# design.net
KiCad netlist of a schematic drawn in Altium Designer
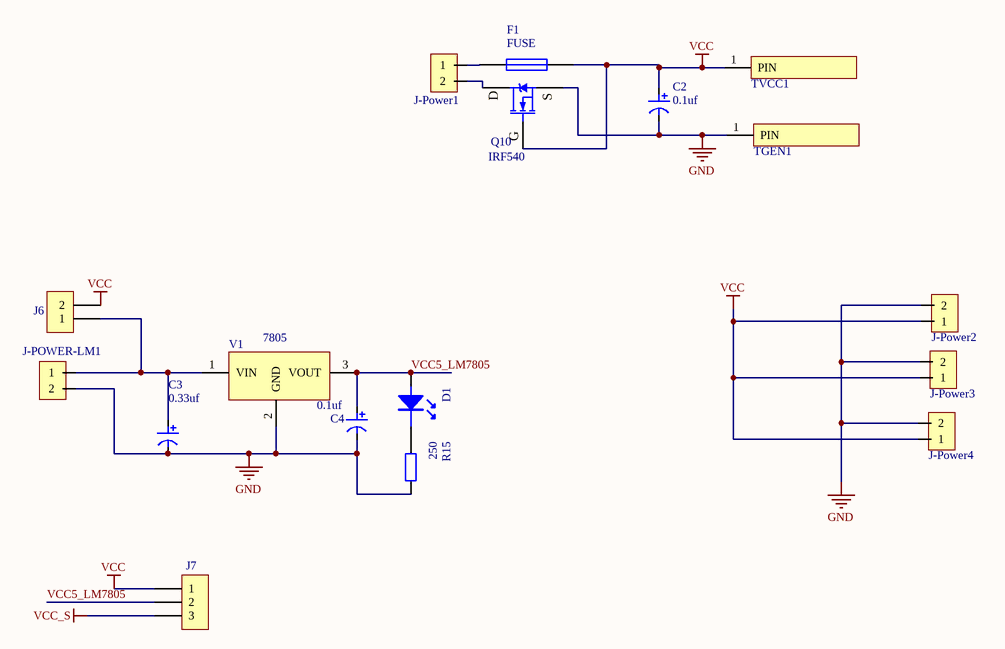
[diagram p0: 电源.SchDoc]

(export (version "E")
  (design (tool "Eeschema 10.0.6"))
  (components
    (comp (ref "C2")
      (value "0.1uf")
      (footprint "CE5-6R5X5-1mm")
      (description "DIP,电容量681pf,额定电压2000V,偏差±10%,6.5X5mm")
      (fields
        (field (name "PART NUMBER") "102CB-00002OD.01")
        (field (name "ALLOW ALTENATIVE PART") "Y")
        (field (name "REMARK") "Verified by BU1（黄雄青） check list V1.0")
        (field (name "MODIFY TIME") "2015年11月05号")
        (field (name "APPROVED") "YES")
      )
      (libsource (lib "IA-04") (part "CAP_Alum-2-N2"))
    )
    (comp (ref "C3")
      (value "0.33uf")
      (footprint "CE5-6R5X5-1mm")
      (description "DIP,电容量681pf,额定电压2000V,偏差±10%,6.5X5mm")
      (fields
        (field (name "PART NUMBER") "102CB-00002OD.01")
        (field (name "ALLOW ALTENATIVE PART") "Y")
        (field (name "REMARK") "Verified by BU1（黄雄青） check list V1.0")
        (field (name "MODIFY TIME") "2015年11月05号")
        (field (name "APPROVED") "YES")
      )
      (libsource (lib "IA-04") (part "CAP_Alum-2-N2"))
    )
    (comp (ref "C4")
      (value "0.1uf")
      (footprint "CE5-6R5X5-1mm")
      (description "DIP,电容量681pf,额定电压2000V,偏差±10%,6.5X5mm")
      (fields
        (field (name "PART NUMBER") "102CB-00002OD.01")
        (field (name "ALLOW ALTENATIVE PART") "Y")
        (field (name "REMARK") "Verified by BU1（黄雄青） check list V1.0")
        (field (name "MODIFY TIME") "2015年11月05号")
        (field (name "APPROVED") "YES")
      )
      (libsource (lib "IA-04") (part "CAP_Alum-2-N2"))
    )
    (comp (ref "D1")
      (value "333-2SYGD/S530-E2")
      (footprint "LED2-D5R9X8R7")
      (description "DIP,封装/间距直径5/2.54mm,额定电压2V,亮度普亮,绿色")
      (fields
        (field (name "PART NUMBER") "102DL-00010CH.01")
        (field (name "ALLOW ALTENATIVE PART") "Y")
        (field (name "REMARK") "Verified by CRD（张宗良） check list V1.0")
        (field (name "MODIFY TIME") "2015年11月11号")
        (field (name "APPROVED") "YES")
      )
      (libsource (lib "IA-04") (part "Diode-LED-2-N2"))
    )
    (comp (ref "F1")
      (value "FUSE")
      (footprint "FUSE-24R1X3RX29R7-TH")
      (description "DIP,24.1x29.7x3.0mm,额定电压30V,额定电流9A,触发电流18A,中速断")
      (fields
        (field (name "PART NUMBER") "102FP-00037BI.01")
        (field (name "ALLOW ALTENATIVE PART") "Y")
        (field (name "REMARK") "Verified by BU1（黄雄青） check list V1.0")
        (field (name "MODIFY TIME") "2015年07月10号")
        (field (name "APPROVED") "YES")
      )
      (libsource (lib "IA-04") (part "Fuse-2-NP"))
    )
    (comp (ref "J-POWER-LM1")
      (value "KF301-5.08-2p")
      (footprint "KF301-5.0-2P")
      (libsource (lib "") (part "KF301_1"))
    )
    (comp (ref "J-Power1")
      (value "KF301-5.08-2p")
      (footprint "KF301-5.0-2P")
      (libsource (lib "") (part "KF301_1"))
    )
    (comp (ref "J-Power2")
      (value "KF301-5.08-2p")
      (footprint "KF301-5.0-2P")
      (libsource (lib "KF接口") (part "KF301"))
    )
    (comp (ref "J-Power3")
      (value "KF301-5.08-2p")
      (footprint "KF301-5.0-2P")
      (libsource (lib "KF接口") (part "KF301"))
    )
    (comp (ref "J-Power4")
      (value "KF301-5.08-2p")
      (footprint "KF301-5.0-2P")
      (libsource (lib "KF接口") (part "KF301"))
    )
    (comp (ref "J6")
      (value "PAS1251-0201A01B1BA")
      (footprint "CON2P-2R54-TH")
      (description "DIP,封装脚距2.54mm,180度,1x2PIN,上针/下针6.0/3.0mm,黑色")
      (fields
        (field (name "PART NUMBER") "102NL-00005DJ.01")
        (field (name "ALLOW ALTENATIVE PART") "Y")
        (field (name "REMARK") "Verified by BU2（叶俊雄） check list V1.0")
        (field (name "MODIFY TIME") "2016年08月22号")
        (field (name "APPROVED") "YES")
      )
      (libsource (lib "IA-04") (part "CON2P-NP"))
    )
    (comp (ref "J7")
      (value "PAS1251-0301A01B1BA")
      (footprint "CON3P-2R54-TH")
      (description "DIP,封装脚距2.54mm,180度,1x3PIN,黑色")
      (fields
        (field (name "PART NUMBER") "102NL-00001DJ.01")
        (field (name "ALLOW ALTENATIVE PART") "Y")
        (field (name "REMARK") "Verified by CRD（赖程奇） check list V1.0")
        (field (name "MODIFY TIME") "2016年1月11号")
        (field (name "APPROVED") "YES")
      )
      (libsource (lib "IA-04") (part "CON3-NP"))
    )
    (comp (ref "Q10")
      (value "IRF540")
      (footprint "TO220A")
      (description "N沟场效应管")
      (fields (field (name "版权归属") "源创客"))
      (libsource (lib "6.1   - 场效应管-可控硅") (part "IRF840"))
    )
    (comp (ref "R15")
      (value "250")
      (footprint "RY0R25W")
      (description "DIP,阻值500R,精度±0.1%,4.75x1.65mm,额定功率1/4W")
      (fields
        (field (name "PART NUMBER") "102RO-00087BS.01")
        (field (name "ALLOW ALTENATIVE PART") "Y")
        (field (name "REMARK") "Verified by BU3（吴明徽）check list V1.0")
        (field (name "MODIFY TIME") "2015年11月30号")
        (field (name "APPROVED") "YES")
      )
      (libsource (lib "IA-04") (part "RES-2-NP"))
    )
    (comp (ref "TGEN1")
      (value "T？")
      (footprint "铺铜条")
      (description "2mm*20的铜条用于焊接")
      (libsource (lib "KF接口") (part "铺铜条"))
    )
    (comp (ref "TVCC1")
      (value "T？")
      (footprint "铺铜条")
      (description "2mm*20的铜条用于焊接")
      (libsource (lib "KF接口") (part "铺铜条"))
    )
    (comp (ref "V1")
      (value "7805")
      (footprint "TO220A")
      (description "线性稳压芯片")
      (fields (field (name "版权归属") "源创客"))
      (libsource (lib "1.3   - 电源类芯片") (part "78xx"))
    )
  )
  (nets
    (net (code "1") (name "/VCC5_LM7805") (class "Default")
      (node (ref "C4") (pin "1") (pinfunction "1_1") (pintype "passive"))
      (node (ref "D1") (pin "1") (pinfunction "1_1") (pintype "passive"))
      (node (ref "J7") (pin "2") (pinfunction "2_2") (pintype "passive"))
      (node (ref "V1") (pin "3") (pinfunction "VOUT_3") (pintype "passive"))
    )
    (net (code "2") (name "GND") (class "Default")
      (node (ref "C2") (pin "2") (pinfunction "2_2") (pintype "passive"))
      (node (ref "C3") (pin "2") (pinfunction "2_2") (pintype "passive"))
      (node (ref "C4") (pin "2") (pinfunction "2_2") (pintype "passive"))
      (node (ref "J-POWER-LM1") (pin "2") (pinfunction "2_2") (pintype "passive"))
      (node (ref "J-Power2") (pin "2") (pinfunction "2_2") (pintype "passive"))
      (node (ref "J-Power3") (pin "2") (pinfunction "2_2") (pintype "passive"))
      (node (ref "J-Power4") (pin "2") (pinfunction "2_2") (pintype "passive"))
      (node (ref "Q10") (pin "3") (pinfunction "S_3") (pintype "passive"))
      (node (ref "R15") (pin "2") (pinfunction "2_2") (pintype "passive"))
      (node (ref "TGEN1") (pin "1") (pinfunction "PIN_1") (pintype "passive"))
      (node (ref "V1") (pin "2") (pinfunction "GND_2") (pintype "passive"))
    )
    (net (code "3") (name "Net-(D1-Pad2)") (class "Default")
      (node (ref "D1") (pin "2") (pinfunction "2_2") (pintype "passive"))
      (node (ref "R15") (pin "1") (pinfunction "1_1") (pintype "passive"))
    )
    (net (code "4") (name "Net-(F1-Pad1)") (class "Default")
      (node (ref "F1") (pin "1") (pinfunction "1_1") (pintype "passive"))
      (node (ref "J-Power1") (pin "1") (pinfunction "1_1") (pintype "passive"))
    )
    (net (code "5") (name "Net-(Q10-D)") (class "Default")
      (node (ref "J-Power1") (pin "2") (pinfunction "2_2") (pintype "passive"))
      (node (ref "Q10") (pin "2") (pinfunction "D_2") (pintype "passive"))
    )
    (net (code "6") (name "Net-(V1-VIN)") (class "Default")
      (node (ref "C3") (pin "1") (pinfunction "1_1") (pintype "passive"))
      (node (ref "J-POWER-LM1") (pin "1") (pinfunction "1_1") (pintype "passive"))
      (node (ref "J6") (pin "1") (pinfunction "1_1") (pintype "passive"))
      (node (ref "V1") (pin "1") (pinfunction "VIN_1") (pintype "passive"))
    )
    (net (code "7") (name "VCC") (class "Default")
      (node (ref "C2") (pin "1") (pinfunction "1_1") (pintype "passive"))
      (node (ref "F1") (pin "2") (pinfunction "2_2") (pintype "passive"))
      (node (ref "J-Power2") (pin "1") (pinfunction "1_1") (pintype "passive"))
      (node (ref "J-Power3") (pin "1") (pinfunction "1_1") (pintype "passive"))
      (node (ref "J-Power4") (pin "1") (pinfunction "1_1") (pintype "passive"))
      (node (ref "J6") (pin "2") (pinfunction "2_2") (pintype "passive"))
      (node (ref "J7") (pin "1") (pinfunction "1_1") (pintype "passive"))
      (node (ref "Q10") (pin "1") (pinfunction "G_1") (pintype "passive"))
      (node (ref "TVCC1") (pin "1") (pinfunction "PIN_1") (pintype "passive"))
    )
    (net (code "8") (name "VCC_S") (class "Default")
      (node (ref "J7") (pin "3") (pinfunction "3_3") (pintype "passive"))
    )
  )
)
